# spinner.net
KiCad netlist of a schematic drawn in EAGLE
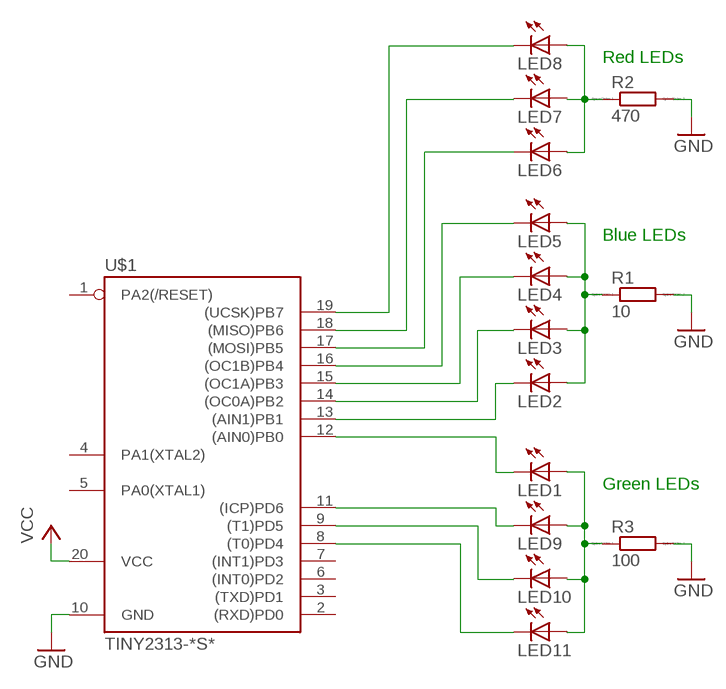
[diagram p0: schematic, sheet 1]

(export (version "E")
  (design (tool "Eeschema 10.0.6"))
  (components
    (comp (ref "LED1")
      (value "TLLG4400")
      (footprint "eagle-import:LED3MM")
      (fields (field (name "MF") "VISHAY SEMICONDUCTOR"))
      (libsource (lib "eagle-import") (part "TLLG4400"))
    )
    (comp (ref "LED2")
      (value "TLLG4400")
      (footprint "eagle-import:LED3MM")
      (fields (field (name "MF") "VISHAY SEMICONDUCTOR"))
      (libsource (lib "eagle-import") (part "TLLG4400"))
    )
    (comp (ref "LED3")
      (value "TLLG4400")
      (footprint "eagle-import:LED3MM")
      (fields (field (name "MF") "VISHAY SEMICONDUCTOR"))
      (libsource (lib "eagle-import") (part "TLLG4400"))
    )
    (comp (ref "LED4")
      (value "TLLG4400")
      (footprint "eagle-import:LED3MM")
      (fields (field (name "MF") "VISHAY SEMICONDUCTOR"))
      (libsource (lib "eagle-import") (part "TLLG4400"))
    )
    (comp (ref "LED5")
      (value "TLLG4400")
      (footprint "eagle-import:LED3MM")
      (fields (field (name "MF") "VISHAY SEMICONDUCTOR"))
      (libsource (lib "eagle-import") (part "TLLG4400"))
    )
    (comp (ref "LED6")
      (value "TLLG4400")
      (footprint "eagle-import:LED3MM")
      (fields (field (name "MF") "VISHAY SEMICONDUCTOR"))
      (libsource (lib "eagle-import") (part "TLLG4400"))
    )
    (comp (ref "LED7")
      (value "TLLG4400")
      (footprint "eagle-import:LED3MM")
      (fields (field (name "MF") "VISHAY SEMICONDUCTOR"))
      (libsource (lib "eagle-import") (part "TLLG4400"))
    )
    (comp (ref "LED8")
      (value "TLLG4400")
      (footprint "eagle-import:LED3MM")
      (fields (field (name "MF") "VISHAY SEMICONDUCTOR"))
      (libsource (lib "eagle-import") (part "TLLG4400"))
    )
    (comp (ref "LED9")
      (value "TLLG4400")
      (footprint "eagle-import:LED3MM")
      (fields (field (name "MF") "VISHAY SEMICONDUCTOR"))
      (libsource (lib "eagle-import") (part "TLLG4400"))
    )
    (comp (ref "LED10")
      (value "TLLG4400")
      (footprint "eagle-import:LED3MM")
      (fields (field (name "MF") "VISHAY SEMICONDUCTOR"))
      (libsource (lib "eagle-import") (part "TLLG4400"))
    )
    (comp (ref "LED11")
      (value "TLLG4400")
      (footprint "eagle-import:LED3MM")
      (fields (field (name "MF") "VISHAY SEMICONDUCTOR"))
      (libsource (lib "eagle-import") (part "TLLG4400"))
    )
    (comp (ref "R1")
      (value "10")
      (footprint "eagle-import:0207_10")
      (libsource (lib "eagle-import") (part "R0207/10"))
    )
    (comp (ref "R2")
      (value "470")
      (footprint "eagle-import:0207_10")
      (libsource (lib "eagle-import") (part "R0207/10"))
    )
    (comp (ref "R3")
      (value "100")
      (footprint "eagle-import:0207_10")
      (libsource (lib "eagle-import") (part "R0207/10"))
    )
    (comp (ref "U$1")
      (value "TINY2313-*S*")
      (footprint "eagle-import:SO20L$")
      (libsource (lib "eagle-import") (part "TINY2313-S"))
    )
  )
  (nets
    (net (code "1") (name "GND") (class "Default")
      (node (ref "R1") (pin "2") (pinfunction "2_2") (pintype "passive"))
      (node (ref "R2") (pin "2") (pinfunction "2_2") (pintype "passive"))
      (node (ref "R3") (pin "2") (pinfunction "2_2") (pintype "passive"))
      (node (ref "U$1") (pin "10") (pinfunction "GND_10") (pintype "power_in"))
    )
    (net (code "2") (name "VCC") (class "Default")
      (node (ref "U$1") (pin "20") (pinfunction "VCC_20") (pintype "power_in"))
    )
    (net (code "3") (name "unconnected-(LED1-C-PadK)") (class "Default")
      (node (ref "LED1") (pin "K") (pinfunction "C_K") (pintype "passive"))
    )
    (net (code "4") (name "unconnected-(LED1-PadA)") (class "Default")
      (node (ref "LED1") (pin "A") (pinfunction "A_A") (pintype "passive"))
    )
    (net (code "5") (name "unconnected-(LED2-C-PadK)") (class "Default")
      (node (ref "LED2") (pin "K") (pinfunction "C_K") (pintype "passive"))
    )
    (net (code "6") (name "unconnected-(LED2-PadA)") (class "Default")
      (node (ref "LED2") (pin "A") (pinfunction "A_A") (pintype "passive"))
    )
    (net (code "7") (name "unconnected-(LED3-C-PadK)") (class "Default")
      (node (ref "LED3") (pin "K") (pinfunction "C_K") (pintype "passive"))
    )
    (net (code "8") (name "unconnected-(LED3-PadA)") (class "Default")
      (node (ref "LED3") (pin "A") (pinfunction "A_A") (pintype "passive"))
    )
    (net (code "9") (name "unconnected-(LED4-C-PadK)") (class "Default")
      (node (ref "LED4") (pin "K") (pinfunction "C_K") (pintype "passive"))
    )
    (net (code "10") (name "unconnected-(LED4-PadA)") (class "Default")
      (node (ref "LED4") (pin "A") (pinfunction "A_A") (pintype "passive"))
    )
    (net (code "11") (name "unconnected-(LED5-C-PadK)") (class "Default")
      (node (ref "LED5") (pin "K") (pinfunction "C_K") (pintype "passive"))
    )
    (net (code "12") (name "unconnected-(LED5-PadA)") (class "Default")
      (node (ref "LED5") (pin "A") (pinfunction "A_A") (pintype "passive"))
    )
    (net (code "13") (name "unconnected-(LED6-C-PadK)") (class "Default")
      (node (ref "LED6") (pin "K") (pinfunction "C_K") (pintype "passive"))
    )
    (net (code "14") (name "unconnected-(LED6-PadA)") (class "Default")
      (node (ref "LED6") (pin "A") (pinfunction "A_A") (pintype "passive"))
    )
    (net (code "15") (name "unconnected-(LED7-C-PadK)") (class "Default")
      (node (ref "LED7") (pin "K") (pinfunction "C_K") (pintype "passive"))
    )
    (net (code "16") (name "unconnected-(LED7-PadA)") (class "Default")
      (node (ref "LED7") (pin "A") (pinfunction "A_A") (pintype "passive"))
    )
    (net (code "17") (name "unconnected-(LED8-C-PadK)") (class "Default")
      (node (ref "LED8") (pin "K") (pinfunction "C_K") (pintype "passive"))
    )
    (net (code "18") (name "unconnected-(LED8-PadA)") (class "Default")
      (node (ref "LED8") (pin "A") (pinfunction "A_A") (pintype "passive"))
    )
    (net (code "19") (name "unconnected-(LED9-C-PadK)") (class "Default")
      (node (ref "LED9") (pin "K") (pinfunction "C_K") (pintype "passive"))
    )
    (net (code "20") (name "unconnected-(LED9-PadA)") (class "Default")
      (node (ref "LED9") (pin "A") (pinfunction "A_A") (pintype "passive"))
    )
    (net (code "21") (name "unconnected-(LED10-C-PadK)") (class "Default")
      (node (ref "LED10") (pin "K") (pinfunction "C_K") (pintype "passive"))
    )
    (net (code "22") (name "unconnected-(LED10-PadA)") (class "Default")
      (node (ref "LED10") (pin "A") (pinfunction "A_A") (pintype "passive"))
    )
    (net (code "23") (name "unconnected-(LED11-C-PadK)") (class "Default")
      (node (ref "LED11") (pin "K") (pinfunction "C_K") (pintype "passive"))
    )
    (net (code "24") (name "unconnected-(LED11-PadA)") (class "Default")
      (node (ref "LED11") (pin "A") (pinfunction "A_A") (pintype "passive"))
    )
    (net (code "25") (name "unconnected-(R1-Pad1)") (class "Default")
      (node (ref "R1") (pin "1") (pinfunction "1_1") (pintype "passive"))
    )
    (net (code "26") (name "unconnected-(R2-Pad1)") (class "Default")
      (node (ref "R2") (pin "1") (pinfunction "1_1") (pintype "passive"))
    )
    (net (code "27") (name "unconnected-(R3-Pad1)") (class "Default")
      (node (ref "R3") (pin "1") (pinfunction "1_1") (pintype "passive"))
    )
    (net (code "28") (name "unconnected-(U$1-(AIN0)PB0-Pad12)") (class "Default")
      (node (ref "U$1") (pin "12") (pinfunction "(AIN0)PB0_12") (pintype "bidirectional"))
    )
    (net (code "29") (name "unconnected-(U$1-(AIN1)PB1-Pad13)") (class "Default")
      (node (ref "U$1") (pin "13") (pinfunction "(AIN1)PB1_13") (pintype "bidirectional"))
    )
    (net (code "30") (name "unconnected-(U$1-(ICP)PD6-Pad11)") (class "Default")
      (node (ref "U$1") (pin "11") (pinfunction "(ICP)PD6_11") (pintype "bidirectional"))
    )
    (net (code "31") (name "unconnected-(U$1-(INT0)PD2-Pad6)") (class "Default")
      (node (ref "U$1") (pin "6") (pinfunction "(INT0)PD2_6") (pintype "bidirectional"))
    )
    (net (code "32") (name "unconnected-(U$1-(INT1)PD3-Pad7)") (class "Default")
      (node (ref "U$1") (pin "7") (pinfunction "(INT1)PD3_7") (pintype "bidirectional"))
    )
    (net (code "33") (name "unconnected-(U$1-(MISO)PB6-Pad18)") (class "Default")
      (node (ref "U$1") (pin "18") (pinfunction "(MISO)PB6_18") (pintype "bidirectional"))
    )
    (net (code "34") (name "unconnected-(U$1-(MOSI)PB5-Pad17)") (class "Default")
      (node (ref "U$1") (pin "17") (pinfunction "(MOSI)PB5_17") (pintype "bidirectional"))
    )
    (net (code "35") (name "unconnected-(U$1-(OC0A)PB2-Pad14)") (class "Default")
      (node (ref "U$1") (pin "14") (pinfunction "(OC0A)PB2_14") (pintype "bidirectional"))
    )
    (net (code "36") (name "unconnected-(U$1-(OC1A)PB3-Pad15)") (class "Default")
      (node (ref "U$1") (pin "15") (pinfunction "(OC1A)PB3_15") (pintype "bidirectional"))
    )
    (net (code "37") (name "unconnected-(U$1-(OC1B)PB4-Pad16)") (class "Default")
      (node (ref "U$1") (pin "16") (pinfunction "(OC1B)PB4_16") (pintype "bidirectional"))
    )
    (net (code "38") (name "unconnected-(U$1-(RXD)PD0-Pad2)") (class "Default")
      (node (ref "U$1") (pin "2") (pinfunction "(RXD)PD0_2") (pintype "bidirectional"))
    )
    (net (code "39") (name "unconnected-(U$1-(T0)PD4-Pad8)") (class "Default")
      (node (ref "U$1") (pin "8") (pinfunction "(T0)PD4_8") (pintype "bidirectional"))
    )
    (net (code "40") (name "unconnected-(U$1-(T1)PD5-Pad9)") (class "Default")
      (node (ref "U$1") (pin "9") (pinfunction "(T1)PD5_9") (pintype "bidirectional"))
    )
    (net (code "41") (name "unconnected-(U$1-(TXD)PD1-Pad3)") (class "Default")
      (node (ref "U$1") (pin "3") (pinfunction "(TXD)PD1_3") (pintype "bidirectional"))
    )
    (net (code "42") (name "unconnected-(U$1-(UCSK)PB7-Pad19)") (class "Default")
      (node (ref "U$1") (pin "19") (pinfunction "(UCSK)PB7_19") (pintype "bidirectional"))
    )
    (net (code "43") (name "unconnected-(U$1-PA0(XTAL1)-Pad5)") (class "Default")
      (node (ref "U$1") (pin "5") (pinfunction "PA0(XTAL1)_5") (pintype "bidirectional"))
    )
    (net (code "44") (name "unconnected-(U$1-PA1(XTAL2)-Pad4)") (class "Default")
      (node (ref "U$1") (pin "4") (pinfunction "PA1(XTAL2)_4") (pintype "bidirectional"))
    )
    (net (code "45") (name "unconnected-(U$1-PA2({slash}RESET)-Pad1)") (class "Default")
      (node (ref "U$1") (pin "1") (pinfunction "PA2(/RESET)_1") (pintype "input"))
    )
  )
)
